# wakeup.net
KiCad netlist of a schematic drawn in EAGLE
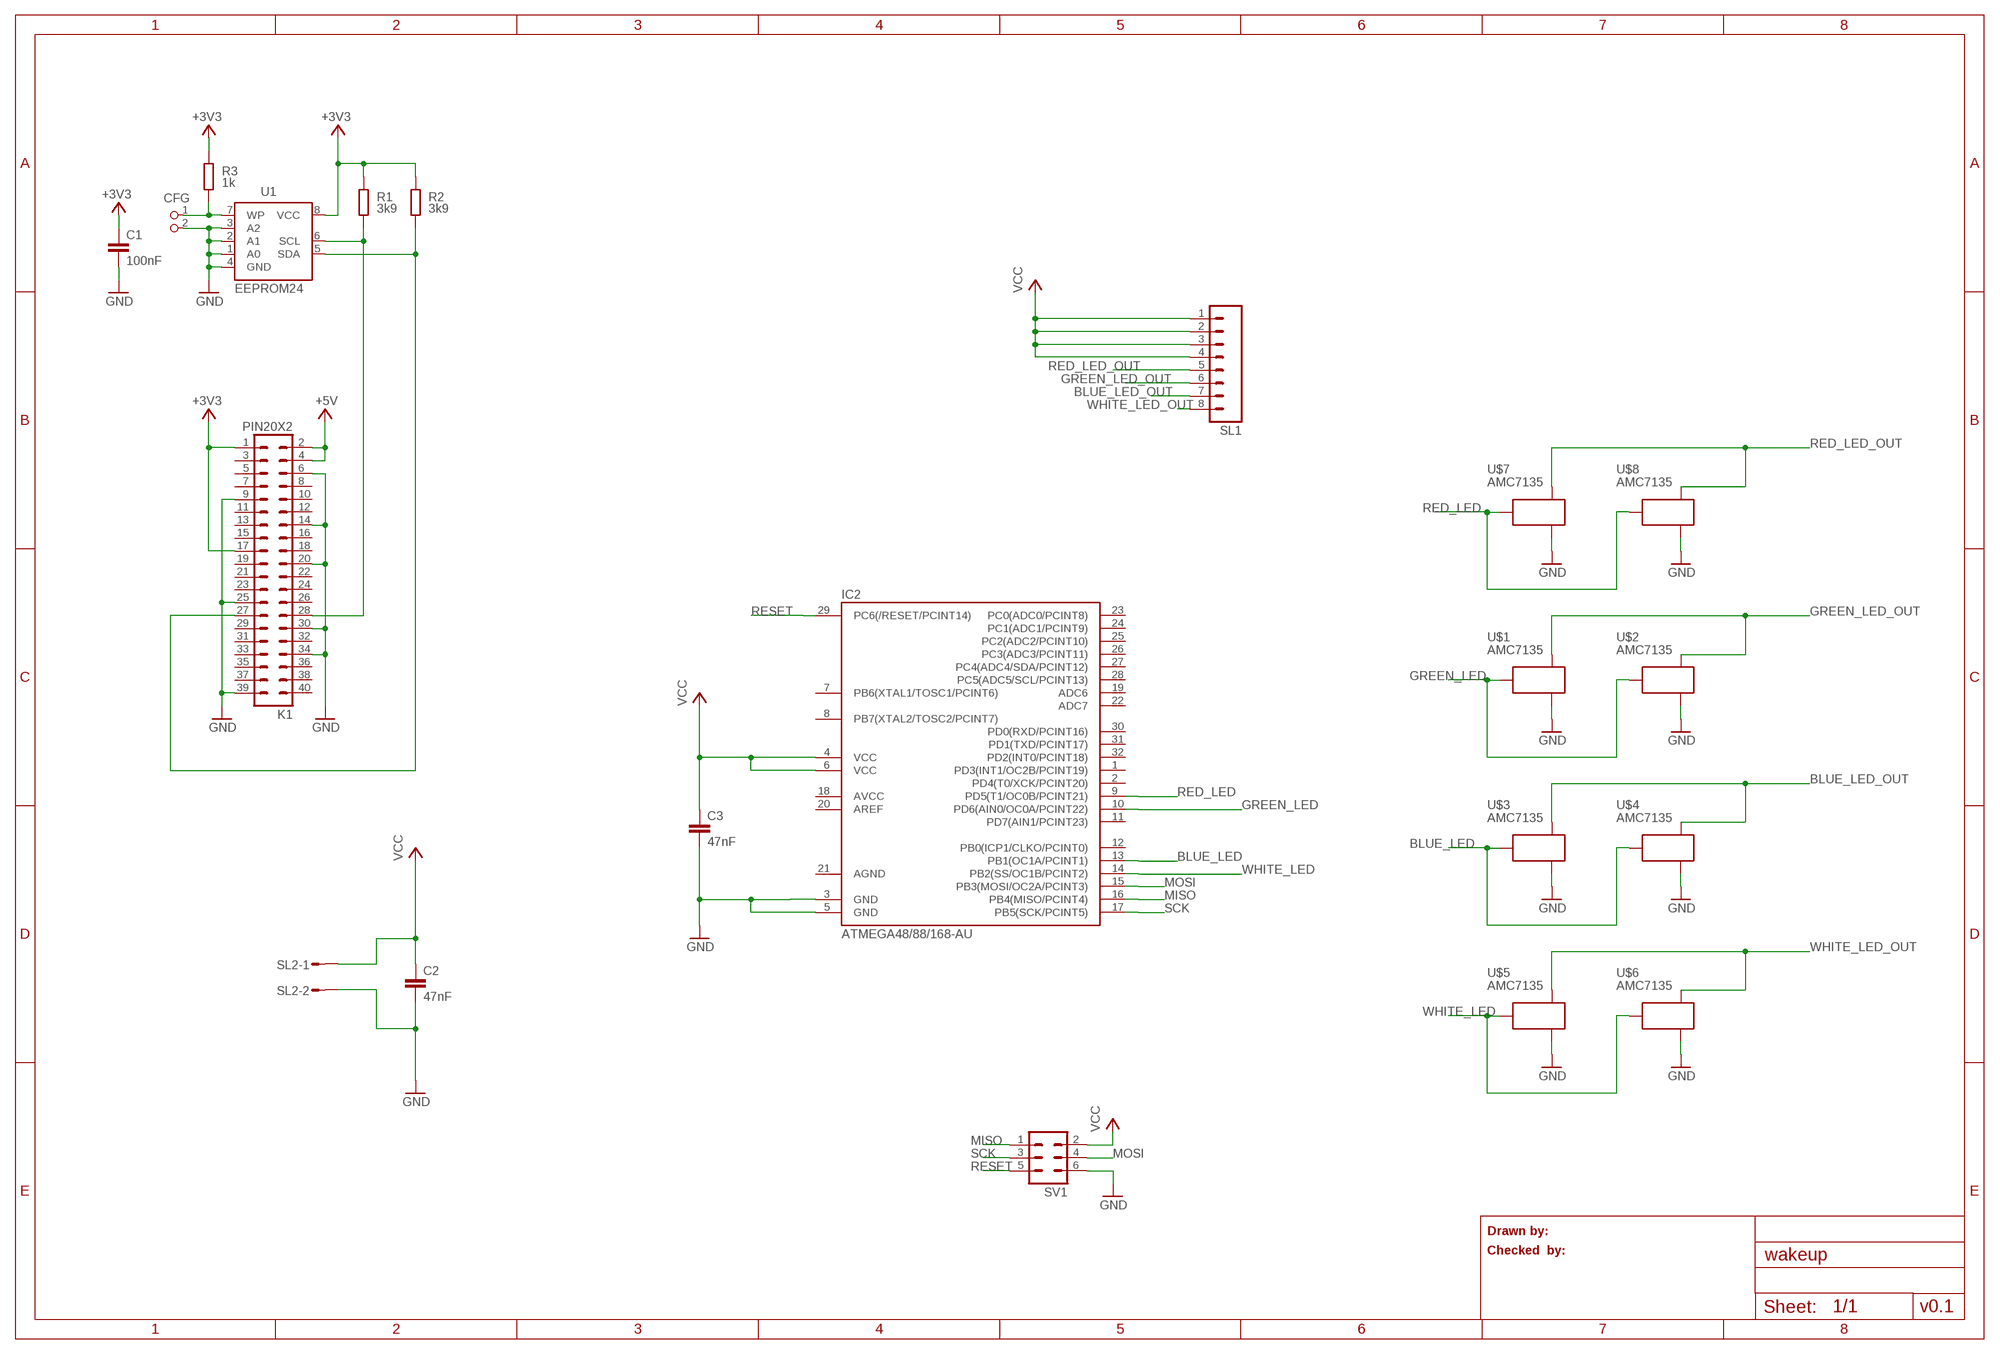
[diagram p0: schematic, sheet 1]

(export (version "E")
  (design (tool "Eeschema 10.0.6"))
  (components
    (comp (ref "C1")
      (value "100nF")
      (footprint "eagle-import:C0805K")
      (libsource (lib "eagle-import") (part "resistor_C-EUC0805K"))
    )
    (comp (ref "C2")
      (value "47nF")
      (footprint "eagle-import:C0805")
      (libsource (lib "eagle-import") (part "C-EUC0805"))
    )
    (comp (ref "C3")
      (value "47nF")
      (footprint "eagle-import:C0805")
      (libsource (lib "eagle-import") (part "C-EUC0805"))
    )
    (comp (ref "CFG")
      (value "PIN2_100")
      (footprint "eagle-import:PIN_W_2")
      (libsource (lib "eagle-import") (part "PIN2_100"))
    )
    (comp (ref "IC2")
      (value "ATMEGA48/88/168-AU")
      (footprint "eagle-import:TQFP32-08")
      (libsource (lib "eagle-import") (part "ATMEGA48/88/168-AU"))
    )
    (comp (ref "K1")
      (value "PIN20X2")
      (footprint "eagle-import:PIN_20X2")
      (libsource (lib "eagle-import") (part "PIN20X2"))
    )
    (comp (ref "R1")
      (value "3k9")
      (footprint "eagle-import:M0805")
      (fields (field (name "TOLERANCE") "5%"))
      (libsource (lib "eagle-import") (part "R-EU_M0805"))
    )
    (comp (ref "R2")
      (value "3k9")
      (footprint "eagle-import:M0805")
      (fields (field (name "TOLERANCE") "5%"))
      (libsource (lib "eagle-import") (part "R-EU_M0805"))
    )
    (comp (ref "R3")
      (value "1k")
      (footprint "eagle-import:M0805")
      (fields (field (name "TOLERANCE") "5%"))
      (libsource (lib "eagle-import") (part "R-EU_M0805"))
    )
    (comp (ref "SL1")
      (value "M08")
      (footprint "eagle-import:08P")
      (libsource (lib "eagle-import") (part "M08"))
    )
    (comp (ref "SL2")
      (value "M02S")
      (footprint "eagle-import:02P")
      (libsource (lib "eagle-import") (part "M02S"))
    )
    (comp (ref "SV1")
      (value "ML6")
      (footprint "eagle-import:ML6")
      (libsource (lib "eagle-import") (part "ML6"))
    )
    (comp (ref "U$1")
      (value "AMC7135")
      (footprint "eagle-import:SOT")
      (libsource (lib "eagle-import") (part "AMC7135"))
    )
    (comp (ref "U$2")
      (value "AMC7135")
      (footprint "eagle-import:SOT")
      (libsource (lib "eagle-import") (part "AMC7135"))
    )
    (comp (ref "U$3")
      (value "AMC7135")
      (footprint "eagle-import:SOT")
      (libsource (lib "eagle-import") (part "AMC7135"))
    )
    (comp (ref "U$4")
      (value "AMC7135")
      (footprint "eagle-import:SOT")
      (libsource (lib "eagle-import") (part "AMC7135"))
    )
    (comp (ref "U$5")
      (value "AMC7135")
      (footprint "eagle-import:SOT")
      (libsource (lib "eagle-import") (part "AMC7135"))
    )
    (comp (ref "U$6")
      (value "AMC7135")
      (footprint "eagle-import:SOT")
      (libsource (lib "eagle-import") (part "AMC7135"))
    )
    (comp (ref "U$7")
      (value "AMC7135")
      (footprint "eagle-import:SOT")
      (libsource (lib "eagle-import") (part "AMC7135"))
    )
    (comp (ref "U$8")
      (value "AMC7135")
      (footprint "eagle-import:SOT")
      (libsource (lib "eagle-import") (part "AMC7135"))
    )
    (comp (ref "U1")
      (value "EEPROM24")
      (footprint "eagle-import:SOIC8")
      (libsource (lib "eagle-import") (part "EEPROM24"))
    )
  )
  (nets
    (net (code "1") (name "+3V3") (class "Default")
      (node (ref "C1") (pin "1") (pinfunction "1_1") (pintype "passive"))
      (node (ref "K1") (pin "1") (pinfunction "1_1") (pintype "passive"))
      (node (ref "K1") (pin "17") (pinfunction "17_17") (pintype "passive"))
      (node (ref "R1") (pin "2") (pinfunction "2_2") (pintype "passive"))
      (node (ref "R2") (pin "2") (pinfunction "2_2") (pintype "passive"))
      (node (ref "R3") (pin "2") (pinfunction "2_2") (pintype "passive"))
      (node (ref "U1") (pin "8") (pinfunction "VCC_8") (pintype "power_in"))
    )
    (net (code "2") (name "+5V") (class "Default")
      (node (ref "K1") (pin "2") (pinfunction "2_2") (pintype "passive"))
      (node (ref "K1") (pin "4") (pinfunction "4_4") (pintype "passive"))
    )
    (net (code "3") (name "/AGND") (class "Default")
      (node (ref "IC2") (pin "21") (pinfunction "AGND_21") (pintype "power_in"))
    )
    (net (code "4") (name "/BLUE_LED") (class "Default")
      (node (ref "IC2") (pin "13") (pinfunction "PB1(OC1A/PCINT1)_13") (pintype "bidirectional"))
      (node (ref "U$3") (pin "3") (pinfunction "VDD_3") (pintype "passive"))
      (node (ref "U$4") (pin "3") (pinfunction "VDD_3") (pintype "passive"))
    )
    (net (code "5") (name "/BLUE_LED_OUT") (class "Default")
      (node (ref "SL1") (pin "7") (pinfunction "7_7") (pintype "passive"))
      (node (ref "U$3") (pin "1") (pinfunction "OUT_1") (pintype "passive"))
      (node (ref "U$4") (pin "1") (pinfunction "OUT_1") (pintype "passive"))
    )
    (net (code "6") (name "/GREEN_LED") (class "Default")
      (node (ref "IC2") (pin "10") (pinfunction "PD6(AIN0/OC0A/PCINT22)_10") (pintype "bidirectional"))
      (node (ref "U$1") (pin "3") (pinfunction "VDD_3") (pintype "passive"))
      (node (ref "U$2") (pin "3") (pinfunction "VDD_3") (pintype "passive"))
    )
    (net (code "7") (name "/GREEN_LED_OUT") (class "Default")
      (node (ref "SL1") (pin "6") (pinfunction "6_6") (pintype "passive"))
      (node (ref "U$1") (pin "1") (pinfunction "OUT_1") (pintype "passive"))
      (node (ref "U$2") (pin "1") (pinfunction "OUT_1") (pintype "passive"))
    )
    (net (code "8") (name "/MISO") (class "Default")
      (node (ref "IC2") (pin "16") (pinfunction "PB4(MISO/PCINT4)_16") (pintype "bidirectional"))
      (node (ref "SV1") (pin "1") (pinfunction "1_1") (pintype "passive"))
    )
    (net (code "9") (name "/MOSI") (class "Default")
      (node (ref "IC2") (pin "15") (pinfunction "PB3(MOSI/OC2A/PCINT3)_15") (pintype "bidirectional"))
      (node (ref "SV1") (pin "4") (pinfunction "4_4") (pintype "passive"))
    )
    (net (code "10") (name "/RED_LED") (class "Default")
      (node (ref "IC2") (pin "9") (pinfunction "PD5(T1/OC0B/PCINT21)_9") (pintype "bidirectional"))
      (node (ref "U$7") (pin "3") (pinfunction "VDD_3") (pintype "passive"))
      (node (ref "U$8") (pin "3") (pinfunction "VDD_3") (pintype "passive"))
    )
    (net (code "11") (name "/RED_LED_OUT") (class "Default")
      (node (ref "SL1") (pin "5") (pinfunction "5_5") (pintype "passive"))
      (node (ref "U$7") (pin "1") (pinfunction "OUT_1") (pintype "passive"))
      (node (ref "U$8") (pin "1") (pinfunction "OUT_1") (pintype "passive"))
    )
    (net (code "12") (name "/RESET") (class "Default")
      (node (ref "IC2") (pin "29") (pinfunction "PC6(/RESET/PCINT14)_29") (pintype "bidirectional"))
      (node (ref "SV1") (pin "5") (pinfunction "5_5") (pintype "passive"))
    )
    (net (code "13") (name "/SCK") (class "Default")
      (node (ref "IC2") (pin "17") (pinfunction "PB5(SCK/PCINT5)_17") (pintype "bidirectional"))
      (node (ref "SV1") (pin "3") (pinfunction "3_3") (pintype "passive"))
    )
    (net (code "14") (name "/WHITE_LED") (class "Default")
      (node (ref "IC2") (pin "14") (pinfunction "PB2(SS/OC1B/PCINT2)_14") (pintype "bidirectional"))
      (node (ref "U$5") (pin "3") (pinfunction "VDD_3") (pintype "passive"))
      (node (ref "U$6") (pin "3") (pinfunction "VDD_3") (pintype "passive"))
    )
    (net (code "15") (name "/WHITE_LED_OUT") (class "Default")
      (node (ref "SL1") (pin "8") (pinfunction "8_8") (pintype "passive"))
      (node (ref "U$5") (pin "1") (pinfunction "OUT_1") (pintype "passive"))
      (node (ref "U$6") (pin "1") (pinfunction "OUT_1") (pintype "passive"))
    )
    (net (code "16") (name "GND") (class "Default")
      (node (ref "C1") (pin "2") (pinfunction "2_2") (pintype "passive"))
      (node (ref "C2") (pin "2") (pinfunction "2_2") (pintype "passive"))
      (node (ref "C3") (pin "2") (pinfunction "2_2") (pintype "passive"))
      (node (ref "CFG") (pin "2") (pinfunction "2_2") (pintype "passive"))
      (node (ref "IC2") (pin "3") (pinfunction "GND_3") (pintype "power_in"))
      (node (ref "IC2") (pin "5") (pinfunction "GND_5") (pintype "power_in"))
      (node (ref "K1") (pin "14") (pinfunction "14_14") (pintype "passive"))
      (node (ref "K1") (pin "20") (pinfunction "20_20") (pintype "passive"))
      (node (ref "K1") (pin "25") (pinfunction "25_25") (pintype "passive"))
      (node (ref "K1") (pin "30") (pinfunction "30_30") (pintype "passive"))
      (node (ref "K1") (pin "34") (pinfunction "34_34") (pintype "passive"))
      (node (ref "K1") (pin "39") (pinfunction "39_39") (pintype "passive"))
      (node (ref "K1") (pin "6") (pinfunction "6_6") (pintype "passive"))
      (node (ref "K1") (pin "9") (pinfunction "9_9") (pintype "passive"))
      (node (ref "SL2") (pin "2") (pinfunction "S_2") (pintype "passive"))
      (node (ref "SV1") (pin "6") (pinfunction "6_6") (pintype "passive"))
      (node (ref "U$1") (pin "2") (pinfunction "GND_2") (pintype "passive"))
      (node (ref "U$1") (pin "2@1") (pinfunction "GND_2@1") (pintype "passive"))
      (node (ref "U$2") (pin "2") (pinfunction "GND_2") (pintype "passive"))
      (node (ref "U$2") (pin "2@1") (pinfunction "GND_2@1") (pintype "passive"))
      (node (ref "U$3") (pin "2") (pinfunction "GND_2") (pintype "passive"))
      (node (ref "U$3") (pin "2@1") (pinfunction "GND_2@1") (pintype "passive"))
      (node (ref "U$4") (pin "2") (pinfunction "GND_2") (pintype "passive"))
      (node (ref "U$4") (pin "2@1") (pinfunction "GND_2@1") (pintype "passive"))
      (node (ref "U$5") (pin "2") (pinfunction "GND_2") (pintype "passive"))
      (node (ref "U$5") (pin "2@1") (pinfunction "GND_2@1") (pintype "passive"))
      (node (ref "U$6") (pin "2") (pinfunction "GND_2") (pintype "passive"))
      (node (ref "U$6") (pin "2@1") (pinfunction "GND_2@1") (pintype "passive"))
      (node (ref "U$7") (pin "2") (pinfunction "GND_2") (pintype "passive"))
      (node (ref "U$7") (pin "2@1") (pinfunction "GND_2@1") (pintype "passive"))
      (node (ref "U$8") (pin "2") (pinfunction "GND_2") (pintype "passive"))
      (node (ref "U$8") (pin "2@1") (pinfunction "GND_2@1") (pintype "passive"))
      (node (ref "U1") (pin "1") (pinfunction "A0_1") (pintype "input"))
      (node (ref "U1") (pin "2") (pinfunction "A1_2") (pintype "input"))
      (node (ref "U1") (pin "3") (pinfunction "A2_3") (pintype "input"))
      (node (ref "U1") (pin "4") (pinfunction "GND_4") (pintype "power_in"))
    )
    (net (code "17") (name "Net-(U1-SCL)") (class "Default")
      (node (ref "K1") (pin "28") (pinfunction "28_28") (pintype "passive"))
      (node (ref "R1") (pin "1") (pinfunction "1_1") (pintype "passive"))
      (node (ref "U1") (pin "6") (pinfunction "SCL_6") (pintype "input"))
    )
    (net (code "18") (name "Net-(U1-SDA)") (class "Default")
      (node (ref "K1") (pin "27") (pinfunction "27_27") (pintype "passive"))
      (node (ref "R2") (pin "1") (pinfunction "1_1") (pintype "passive"))
      (node (ref "U1") (pin "5") (pinfunction "SDA_5") (pintype "bidirectional"))
    )
    (net (code "19") (name "Net-(U1-WP)") (class "Default")
      (node (ref "CFG") (pin "1") (pinfunction "1_1") (pintype "passive"))
      (node (ref "R3") (pin "1") (pinfunction "1_1") (pintype "passive"))
      (node (ref "U1") (pin "7") (pinfunction "WP_7") (pintype "input"))
    )
    (net (code "20") (name "VCC") (class "Default")
      (node (ref "C2") (pin "1") (pinfunction "1_1") (pintype "passive"))
      (node (ref "C3") (pin "1") (pinfunction "1_1") (pintype "passive"))
      (node (ref "IC2") (pin "4") (pinfunction "VCC_4") (pintype "power_in"))
      (node (ref "IC2") (pin "6") (pinfunction "VCC_6") (pintype "power_in"))
      (node (ref "SL1") (pin "1") (pinfunction "1_1") (pintype "passive"))
      (node (ref "SL1") (pin "2") (pinfunction "2_2") (pintype "passive"))
      (node (ref "SL1") (pin "3") (pinfunction "3_3") (pintype "passive"))
      (node (ref "SL1") (pin "4") (pinfunction "4_4") (pintype "passive"))
      (node (ref "SL2") (pin "1") (pinfunction "S_1") (pintype "passive"))
      (node (ref "SV1") (pin "2") (pinfunction "2_2") (pintype "passive"))
    )
    (net (code "21") (name "unconnected-(IC2-ADC6-Pad19)") (class "Default")
      (node (ref "IC2") (pin "19") (pinfunction "ADC6_19") (pintype "passive"))
    )
    (net (code "22") (name "unconnected-(IC2-ADC7-Pad22)") (class "Default")
      (node (ref "IC2") (pin "22") (pinfunction "ADC7_22") (pintype "passive"))
    )
    (net (code "23") (name "unconnected-(IC2-AREF-Pad20)") (class "Default")
      (node (ref "IC2") (pin "20") (pinfunction "AREF_20") (pintype "passive"))
    )
    (net (code "24") (name "unconnected-(IC2-AVCC-Pad18)") (class "Default")
      (node (ref "IC2") (pin "18") (pinfunction "AVCC_18") (pintype "passive"))
    )
    (net (code "25") (name "unconnected-(IC2-PB0(ICP1{slash}CLKO{slash}PCINT0)-Pad12)") (class "Default")
      (node (ref "IC2") (pin "12") (pinfunction "PB0(ICP1/CLKO/PCINT0)_12") (pintype "bidirectional"))
    )
    (net (code "26") (name "unconnected-(IC2-PB6(XTAL1{slash}TOSC1{slash}PCINT6)-Pad7)") (class "Default")
      (node (ref "IC2") (pin "7") (pinfunction "PB6(XTAL1/TOSC1/PCINT6)_7") (pintype "bidirectional"))
    )
    (net (code "27") (name "unconnected-(IC2-PB7(XTAL2{slash}TOSC2{slash}PCINT7)-Pad8)") (class "Default")
      (node (ref "IC2") (pin "8") (pinfunction "PB7(XTAL2/TOSC2/PCINT7)_8") (pintype "bidirectional"))
    )
    (net (code "28") (name "unconnected-(IC2-PC0(ADC0{slash}PCINT8)-Pad23)") (class "Default")
      (node (ref "IC2") (pin "23") (pinfunction "PC0(ADC0/PCINT8)_23") (pintype "bidirectional"))
    )
    (net (code "29") (name "unconnected-(IC2-PC1(ADC1{slash}PCINT9)-Pad24)") (class "Default")
      (node (ref "IC2") (pin "24") (pinfunction "PC1(ADC1/PCINT9)_24") (pintype "bidirectional"))
    )
    (net (code "30") (name "unconnected-(IC2-PC2(ADC2{slash}PCINT10)-Pad25)") (class "Default")
      (node (ref "IC2") (pin "25") (pinfunction "PC2(ADC2/PCINT10)_25") (pintype "bidirectional"))
    )
    (net (code "31") (name "unconnected-(IC2-PC3(ADC3{slash}PCINT11)-Pad26)") (class "Default")
      (node (ref "IC2") (pin "26") (pinfunction "PC3(ADC3/PCINT11)_26") (pintype "bidirectional"))
    )
    (net (code "32") (name "unconnected-(IC2-PC4(ADC4{slash}SDA{slash}PCINT12)-Pad27)") (class "Default")
      (node (ref "IC2") (pin "27") (pinfunction "PC4(ADC4/SDA/PCINT12)_27") (pintype "bidirectional"))
    )
    (net (code "33") (name "unconnected-(IC2-PC5(ADC5{slash}SCL{slash}PCINT13)-Pad28)") (class "Default")
      (node (ref "IC2") (pin "28") (pinfunction "PC5(ADC5/SCL/PCINT13)_28") (pintype "bidirectional"))
    )
    (net (code "34") (name "unconnected-(IC2-PD0(RXD{slash}PCINT16)-Pad30)") (class "Default")
      (node (ref "IC2") (pin "30") (pinfunction "PD0(RXD/PCINT16)_30") (pintype "bidirectional"))
    )
    (net (code "35") (name "unconnected-(IC2-PD1(TXD{slash}PCINT17)-Pad31)") (class "Default")
      (node (ref "IC2") (pin "31") (pinfunction "PD1(TXD/PCINT17)_31") (pintype "bidirectional"))
    )
    (net (code "36") (name "unconnected-(IC2-PD2(INT0{slash}PCINT18)-Pad32)") (class "Default")
      (node (ref "IC2") (pin "32") (pinfunction "PD2(INT0/PCINT18)_32") (pintype "bidirectional"))
    )
    (net (code "37") (name "unconnected-(IC2-PD3(INT1{slash}OC2B{slash}PCINT19)-Pad1)") (class "Default")
      (node (ref "IC2") (pin "1") (pinfunction "PD3(INT1/OC2B/PCINT19)_1") (pintype "bidirectional"))
    )
    (net (code "38") (name "unconnected-(IC2-PD4(T0{slash}XCK{slash}PCINT20)-Pad2)") (class "Default")
      (node (ref "IC2") (pin "2") (pinfunction "PD4(T0/XCK/PCINT20)_2") (pintype "bidirectional"))
    )
    (net (code "39") (name "unconnected-(IC2-PD7(AIN1{slash}PCINT23)-Pad11)") (class "Default")
      (node (ref "IC2") (pin "11") (pinfunction "PD7(AIN1/PCINT23)_11") (pintype "bidirectional"))
    )
    (net (code "40") (name "unconnected-(K1-Pad3)") (class "Default")
      (node (ref "K1") (pin "3") (pinfunction "3_3") (pintype "passive"))
    )
    (net (code "41") (name "unconnected-(K1-Pad5)") (class "Default")
      (node (ref "K1") (pin "5") (pinfunction "5_5") (pintype "passive"))
    )
    (net (code "42") (name "unconnected-(K1-Pad7)") (class "Default")
      (node (ref "K1") (pin "7") (pinfunction "7_7") (pintype "passive"))
    )
    (net (code "43") (name "unconnected-(K1-Pad8)") (class "Default")
      (node (ref "K1") (pin "8") (pinfunction "8_8") (pintype "passive"))
    )
    (net (code "44") (name "unconnected-(K1-Pad10)") (class "Default")
      (node (ref "K1") (pin "10") (pinfunction "10_10") (pintype "passive"))
    )
    (net (code "45") (name "unconnected-(K1-Pad11)") (class "Default")
      (node (ref "K1") (pin "11") (pinfunction "11_11") (pintype "passive"))
    )
    (net (code "46") (name "unconnected-(K1-Pad12)") (class "Default")
      (node (ref "K1") (pin "12") (pinfunction "12_12") (pintype "passive"))
    )
    (net (code "47") (name "unconnected-(K1-Pad13)") (class "Default")
      (node (ref "K1") (pin "13") (pinfunction "13_13") (pintype "passive"))
    )
    (net (code "48") (name "unconnected-(K1-Pad15)") (class "Default")
      (node (ref "K1") (pin "15") (pinfunction "15_15") (pintype "passive"))
    )
    (net (code "49") (name "unconnected-(K1-Pad16)") (class "Default")
      (node (ref "K1") (pin "16") (pinfunction "16_16") (pintype "passive"))
    )
    (net (code "50") (name "unconnected-(K1-Pad18)") (class "Default")
      (node (ref "K1") (pin "18") (pinfunction "18_18") (pintype "passive"))
    )
    (net (code "51") (name "unconnected-(K1-Pad19)") (class "Default")
      (node (ref "K1") (pin "19") (pinfunction "19_19") (pintype "passive"))
    )
    (net (code "52") (name "unconnected-(K1-Pad21)") (class "Default")
      (node (ref "K1") (pin "21") (pinfunction "21_21") (pintype "passive"))
    )
    (net (code "53") (name "unconnected-(K1-Pad22)") (class "Default")
      (node (ref "K1") (pin "22") (pinfunction "22_22") (pintype "passive"))
    )
    (net (code "54") (name "unconnected-(K1-Pad23)") (class "Default")
      (node (ref "K1") (pin "23") (pinfunction "23_23") (pintype "passive"))
    )
    (net (code "55") (name "unconnected-(K1-Pad24)") (class "Default")
      (node (ref "K1") (pin "24") (pinfunction "24_24") (pintype "passive"))
    )
    (net (code "56") (name "unconnected-(K1-Pad26)") (class "Default")
      (node (ref "K1") (pin "26") (pinfunction "26_26") (pintype "passive"))
    )
    (net (code "57") (name "unconnected-(K1-Pad29)") (class "Default")
      (node (ref "K1") (pin "29") (pinfunction "29_29") (pintype "passive"))
    )
    (net (code "58") (name "unconnected-(K1-Pad31)") (class "Default")
      (node (ref "K1") (pin "31") (pinfunction "31_31") (pintype "passive"))
    )
    (net (code "59") (name "unconnected-(K1-Pad32)") (class "Default")
      (node (ref "K1") (pin "32") (pinfunction "32_32") (pintype "passive"))
    )
    (net (code "60") (name "unconnected-(K1-Pad33)") (class "Default")
      (node (ref "K1") (pin "33") (pinfunction "33_33") (pintype "passive"))
    )
    (net (code "61") (name "unconnected-(K1-Pad35)") (class "Default")
      (node (ref "K1") (pin "35") (pinfunction "35_35") (pintype "passive"))
    )
    (net (code "62") (name "unconnected-(K1-Pad36)") (class "Default")
      (node (ref "K1") (pin "36") (pinfunction "36_36") (pintype "passive"))
    )
    (net (code "63") (name "unconnected-(K1-Pad37)") (class "Default")
      (node (ref "K1") (pin "37") (pinfunction "37_37") (pintype "passive"))
    )
    (net (code "64") (name "unconnected-(K1-Pad38)") (class "Default")
      (node (ref "K1") (pin "38") (pinfunction "38_38") (pintype "passive"))
    )
    (net (code "65") (name "unconnected-(K1-Pad40)") (class "Default")
      (node (ref "K1") (pin "40") (pinfunction "40_40") (pintype "passive"))
    )
  )
)
